# BLE2.net
KiCad netlist of a schematic drawn in EasyEDA Pro
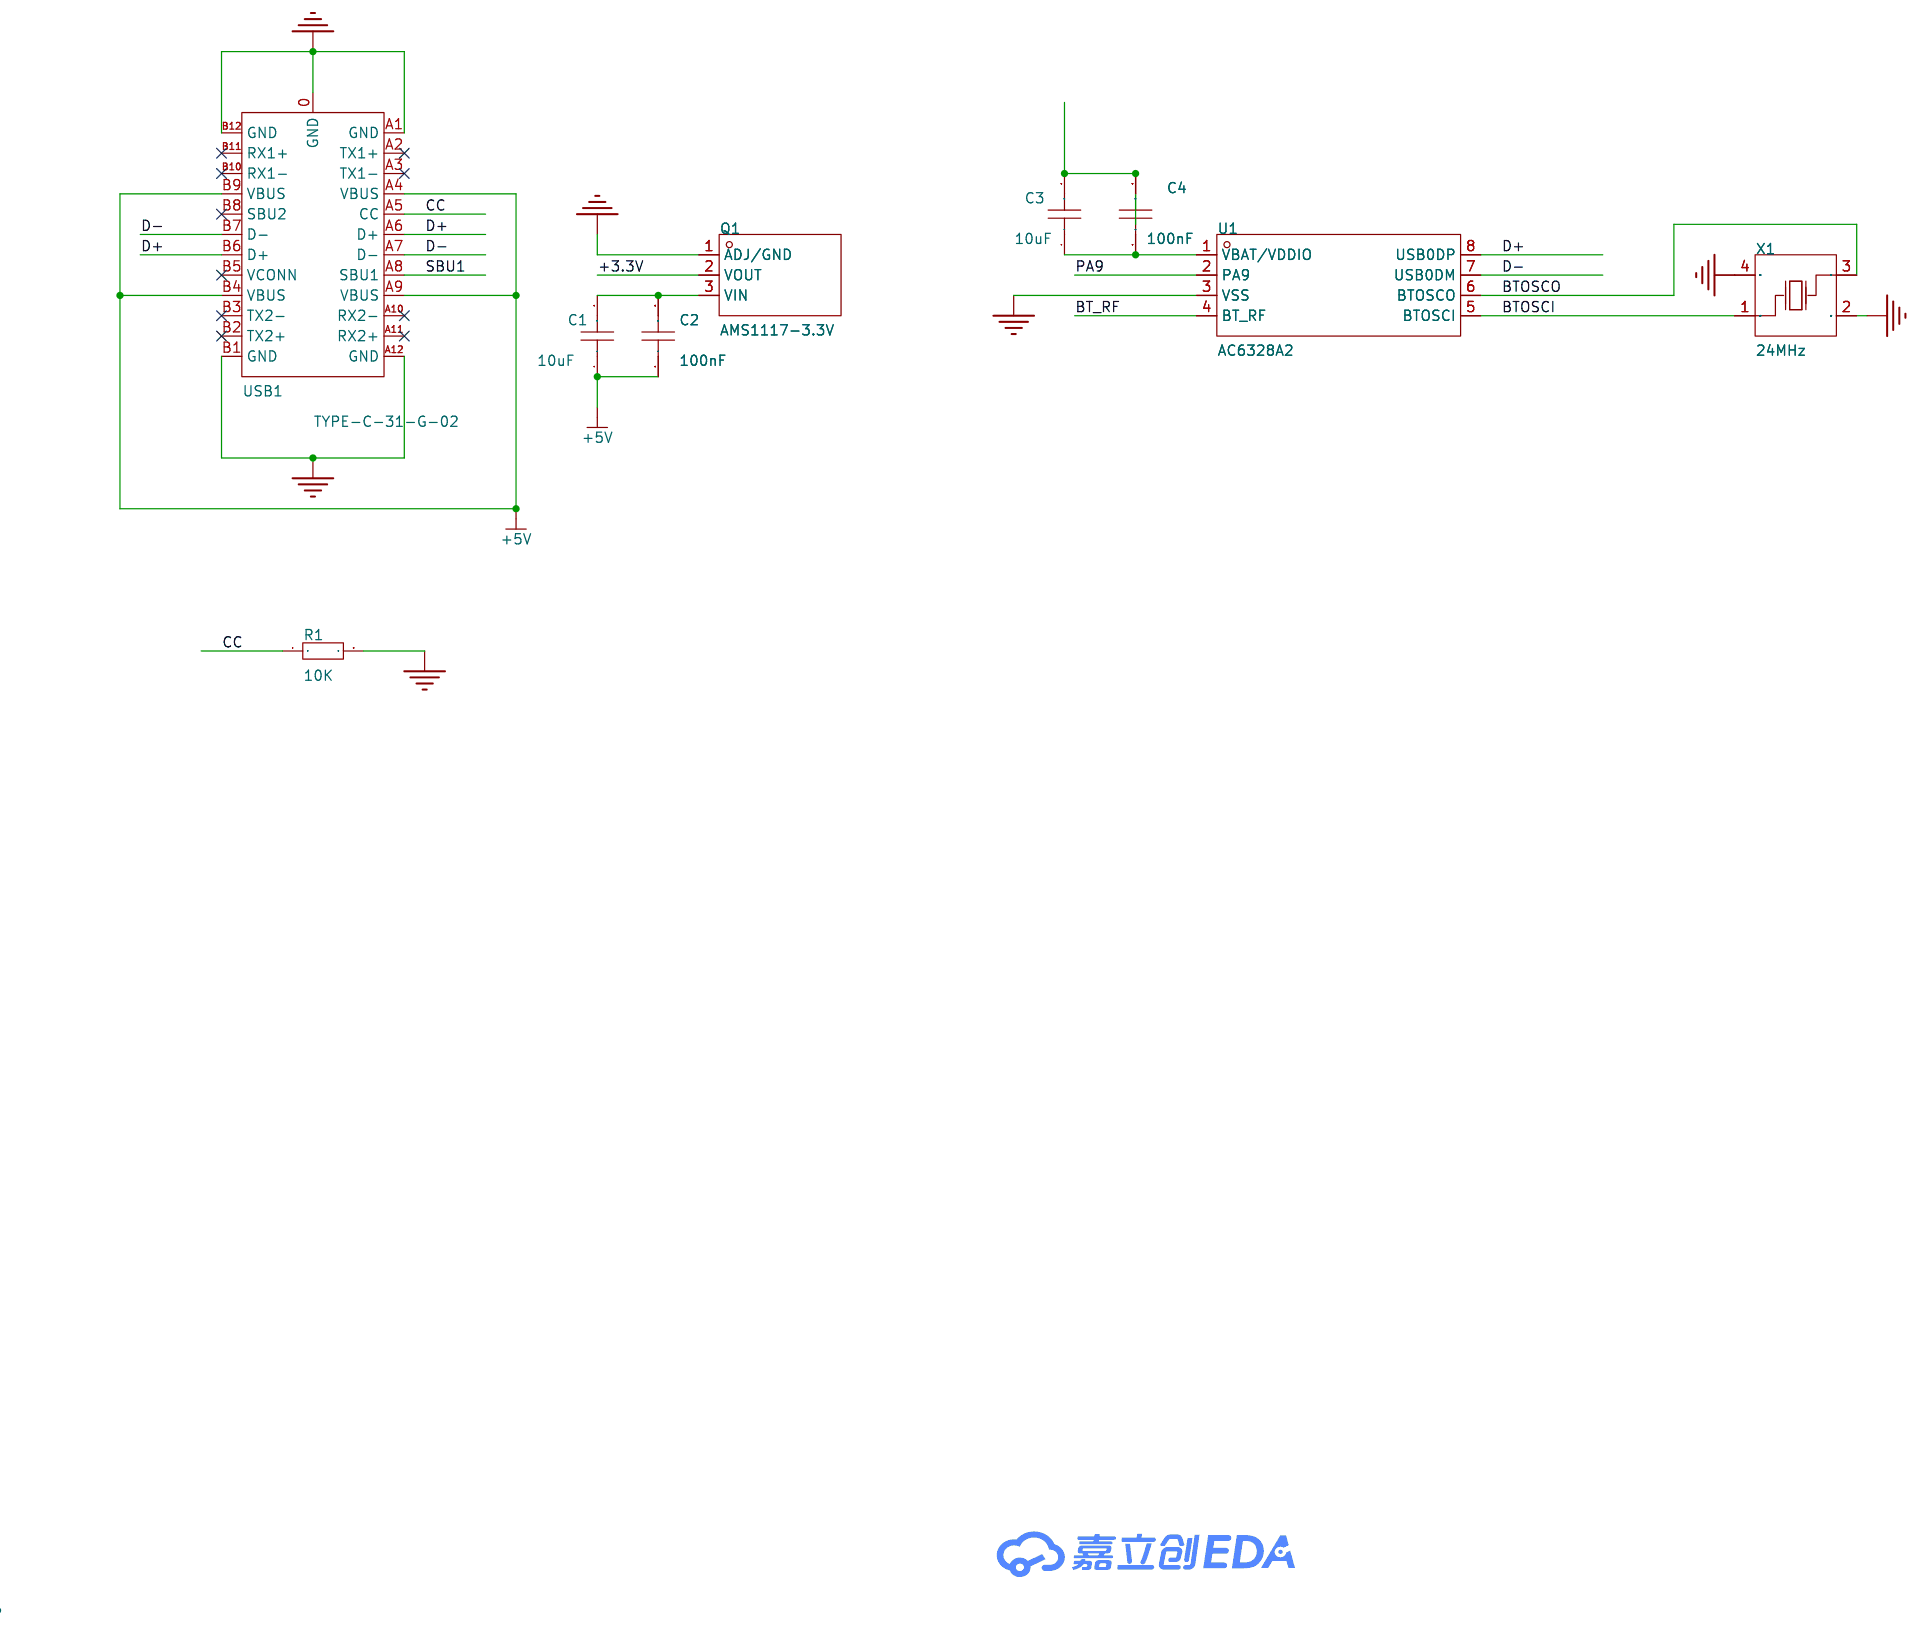
[diagram p0: schematic sheet]

(export (version "E")
  (design (tool "Eeschema 10.0.6"))
  (components
    (comp (ref "C1")
      (value "10uF")
      (footprint "easyedapro:C0603")
      (libsource (lib "easyedapro") (part "Capacitance"))
    )
    (comp (ref "C2")
      (value "100nF")
      (footprint "easyedapro:C0603")
      (libsource (lib "easyedapro") (part "Capacitance"))
    )
    (comp (ref "C3")
      (value "10uF")
      (footprint "easyedapro:C0603")
      (libsource (lib "easyedapro") (part "Capacitance"))
    )
    (comp (ref "C4")
      (value "100nF")
      (footprint "easyedapro:C0603")
      (libsource (lib "easyedapro") (part "Capacitance"))
    )
    (comp (ref "Q1")
      (value "AMS1117-3.3V")
      (footprint "easyedapro:SOT-89-3_L4.5-W2.5-P1.50-LS4.2-BR")
      (description "输出类型:固定;工作电压:18V;输出电压:3.3V;输出电流:1A;输出极性:正极;")
      (fields (field (name "Manufacturer") "MSKSEMI(美森科)"))
      (libsource (lib "easyedapro") (part "AMS1117-3.3V_C5120796"))
    )
    (comp (ref "R1") (value "10K") (footprint "easyedapro:R0402") (libsource (lib "easyedapro") (part "电阻")))
    (comp (ref "U1")
      (value "AC6328A2")
      (footprint "easyedapro:SOP-8_L4.9-W3.9-P1.27-LS6.0-BL")
      (fields (field (name "Manufacturer") "JL(杰理)"))
      (libsource (lib "easyedapro") (part "AC6328A2"))
    )
    (comp (ref "USB1")
      (value "TYPE-C-31-G-02")
      (footprint "easyedapro:USB-C-SMD_TYPE-C-31-G-02")
      (description "连接器类型:Type-C;协议标准:-;公母:公;安装方式:夹板;触点数量:24P;端口数量:1;额定电流 - 电源:-;工作温度:-55°C~+85°C;")
      (fields (field (name "Manufacturer") "韩国韩荣"))
      (libsource (lib "easyedapro") (part "TYPE-C-31-G-02"))
    )
    (comp (ref "X1")
      (value "24MHz")
      (footprint "easyedapro:CRYSTAL-SMD_4P-L3.2-W2.5-BL")
      (description "晶振类型:贴片晶振;频率:24MHz;常温频差:±10ppm;负载电容:12pF;频率稳定度:±20ppm;")
      (fields (field (name "Manufacturer Part") "X322524MOB4SI") (field (name "Manufacturer") "YXC(扬兴晶振)"))
      (libsource (lib "easyedapro") (part "X322524MOB4SI"))
    )
  )
  (nets
    (net (code "1") (name "+5V") (class "Default")
      (node (ref "C1") (pin "1") (pinfunction "1_1") (pintype "input"))
      (node (ref "C2") (pin "1") (pinfunction "1_1") (pintype "input"))
      (node (ref "USB1") (pin "A4") (pinfunction "VBUS_A4") (pintype "unspecified"))
      (node (ref "USB1") (pin "A9") (pinfunction "VBUS_A9") (pintype "unspecified"))
      (node (ref "USB1") (pin "B4") (pinfunction "VBUS_B4") (pintype "unspecified"))
      (node (ref "USB1") (pin "B9") (pinfunction "VBUS_B9") (pintype "unspecified"))
    )
    (net (code "2") (name "/+3.3V") (class "Default")
      (node (ref "Q1") (pin "2") (pinfunction "VOUT_2") (pintype "unspecified"))
    )
    (net (code "3") (name "/BTOSCI") (class "Default")
      (node (ref "U1") (pin "5") (pinfunction "BTOSCI_5") (pintype "unspecified"))
      (node (ref "X1") (pin "1") (pinfunction "OSC1_1") (pintype "unspecified"))
    )
    (net (code "4") (name "/BTOSCO") (class "Default")
      (node (ref "U1") (pin "6") (pinfunction "BTOSCO_6") (pintype "unspecified"))
      (node (ref "X1") (pin "3") (pinfunction "OSC2_3") (pintype "unspecified"))
    )
    (net (code "5") (name "/BT_RF") (class "Default")
      (node (ref "U1") (pin "4") (pinfunction "BT_RF_4") (pintype "unspecified"))
    )
    (net (code "6") (name "/CC") (class "Default")
      (node (ref "R1") (pin "1") (pinfunction "1_1") (pintype "input"))
      (node (ref "USB1") (pin "A5") (pinfunction "CC_A5") (pintype "unspecified"))
    )
    (net (code "7") (name "/D+") (class "Default")
      (node (ref "U1") (pin "8") (pinfunction "USB0DP_8") (pintype "unspecified"))
      (node (ref "USB1") (pin "A6") (pinfunction "D+_A6") (pintype "unspecified"))
      (node (ref "USB1") (pin "B6") (pinfunction "D+_B6") (pintype "unspecified"))
    )
    (net (code "8") (name "/D-") (class "Default")
      (node (ref "U1") (pin "7") (pinfunction "USB0DM_7") (pintype "unspecified"))
      (node (ref "USB1") (pin "A7") (pinfunction "D-_A7") (pintype "unspecified"))
      (node (ref "USB1") (pin "B7") (pinfunction "D-_B7") (pintype "unspecified"))
    )
    (net (code "9") (name "/PA9") (class "Default")
      (node (ref "U1") (pin "2") (pinfunction "PA9_2") (pintype "unspecified"))
    )
    (net (code "10") (name "/SBU1") (class "Default")
      (node (ref "USB1") (pin "A8") (pinfunction "SBU1_A8") (pintype "unspecified"))
    )
    (net (code "11") (name "GND") (class "Default")
      (node (ref "Q1") (pin "1") (pinfunction "ADJ/GND_1") (pintype "unspecified"))
      (node (ref "R1") (pin "2") (pinfunction "2_2") (pintype "input"))
      (node (ref "U1") (pin "3") (pinfunction "VSS_3") (pintype "unspecified"))
      (node (ref "USB1") (pin "0") (pinfunction "GND_0") (pintype "unspecified"))
      (node (ref "USB1") (pin "A1") (pinfunction "GND_A1") (pintype "unspecified"))
      (node (ref "USB1") (pin "A12") (pinfunction "GND_A12") (pintype "unspecified"))
      (node (ref "USB1") (pin "B1") (pinfunction "GND_B1") (pintype "unspecified"))
      (node (ref "USB1") (pin "B12") (pinfunction "GND_B12") (pintype "unspecified"))
      (node (ref "X1") (pin "2") (pinfunction "GND_2") (pintype "unspecified"))
      (node (ref "X1") (pin "4") (pinfunction "GND_4") (pintype "unspecified"))
    )
    (net (code "12") (name "Net-(C3-Pad2)") (class "Default")
      (node (ref "C3") (pin "2") (pinfunction "2_2") (pintype "input"))
      (node (ref "C4") (pin "2") (pinfunction "2_2") (pintype "input"))
    )
    (net (code "13") (name "Net-(Q1-VIN)") (class "Default")
      (node (ref "C1") (pin "2") (pinfunction "2_2") (pintype "input"))
      (node (ref "C2") (pin "2") (pinfunction "2_2") (pintype "input"))
      (node (ref "Q1") (pin "3") (pinfunction "VIN_3") (pintype "unspecified"))
    )
    (net (code "14") (name "Net-(U1-VBAT{slash}VDDIO)") (class "Default")
      (node (ref "C3") (pin "1") (pinfunction "1_1") (pintype "input"))
      (node (ref "C4") (pin "1") (pinfunction "1_1") (pintype "input"))
      (node (ref "U1") (pin "1") (pinfunction "VBAT/VDDIO_1") (pintype "unspecified"))
    )
    (net (code "15") (name "unconnected-(USB1-RX1+-PadB11)") (class "Default")
      (node (ref "USB1") (pin "B11") (pinfunction "RX1+_B11") (pintype "unspecified+no_connect"))
    )
    (net (code "16") (name "unconnected-(USB1-RX1--PadB10)") (class "Default")
      (node (ref "USB1") (pin "B10") (pinfunction "RX1-_B10") (pintype "unspecified+no_connect"))
    )
    (net (code "17") (name "unconnected-(USB1-RX2+-PadA11)") (class "Default")
      (node (ref "USB1") (pin "A11") (pinfunction "RX2+_A11") (pintype "unspecified+no_connect"))
    )
    (net (code "18") (name "unconnected-(USB1-RX2--PadA10)") (class "Default")
      (node (ref "USB1") (pin "A10") (pinfunction "RX2-_A10") (pintype "unspecified+no_connect"))
    )
    (net (code "19") (name "unconnected-(USB1-SBU2-PadB8)") (class "Default")
      (node (ref "USB1") (pin "B8") (pinfunction "SBU2_B8") (pintype "unspecified+no_connect"))
    )
    (net (code "20") (name "unconnected-(USB1-TX1+-PadA2)") (class "Default")
      (node (ref "USB1") (pin "A2") (pinfunction "TX1+_A2") (pintype "unspecified+no_connect"))
    )
    (net (code "21") (name "unconnected-(USB1-TX1--PadA3)") (class "Default")
      (node (ref "USB1") (pin "A3") (pinfunction "TX1-_A3") (pintype "unspecified+no_connect"))
    )
    (net (code "22") (name "unconnected-(USB1-TX2+-PadB2)") (class "Default")
      (node (ref "USB1") (pin "B2") (pinfunction "TX2+_B2") (pintype "unspecified+no_connect"))
    )
    (net (code "23") (name "unconnected-(USB1-TX2--PadB3)") (class "Default")
      (node (ref "USB1") (pin "B3") (pinfunction "TX2-_B3") (pintype "unspecified+no_connect"))
    )
    (net (code "24") (name "unconnected-(USB1-VCONN-PadB5)") (class "Default")
      (node (ref "USB1") (pin "B5") (pinfunction "VCONN_B5") (pintype "unspecified+no_connect"))
    )
  )
)
